# UPCNSL-ABS-PVC-DEP-1A.net
KiCad netlist of a schematic drawn in Altium Designer
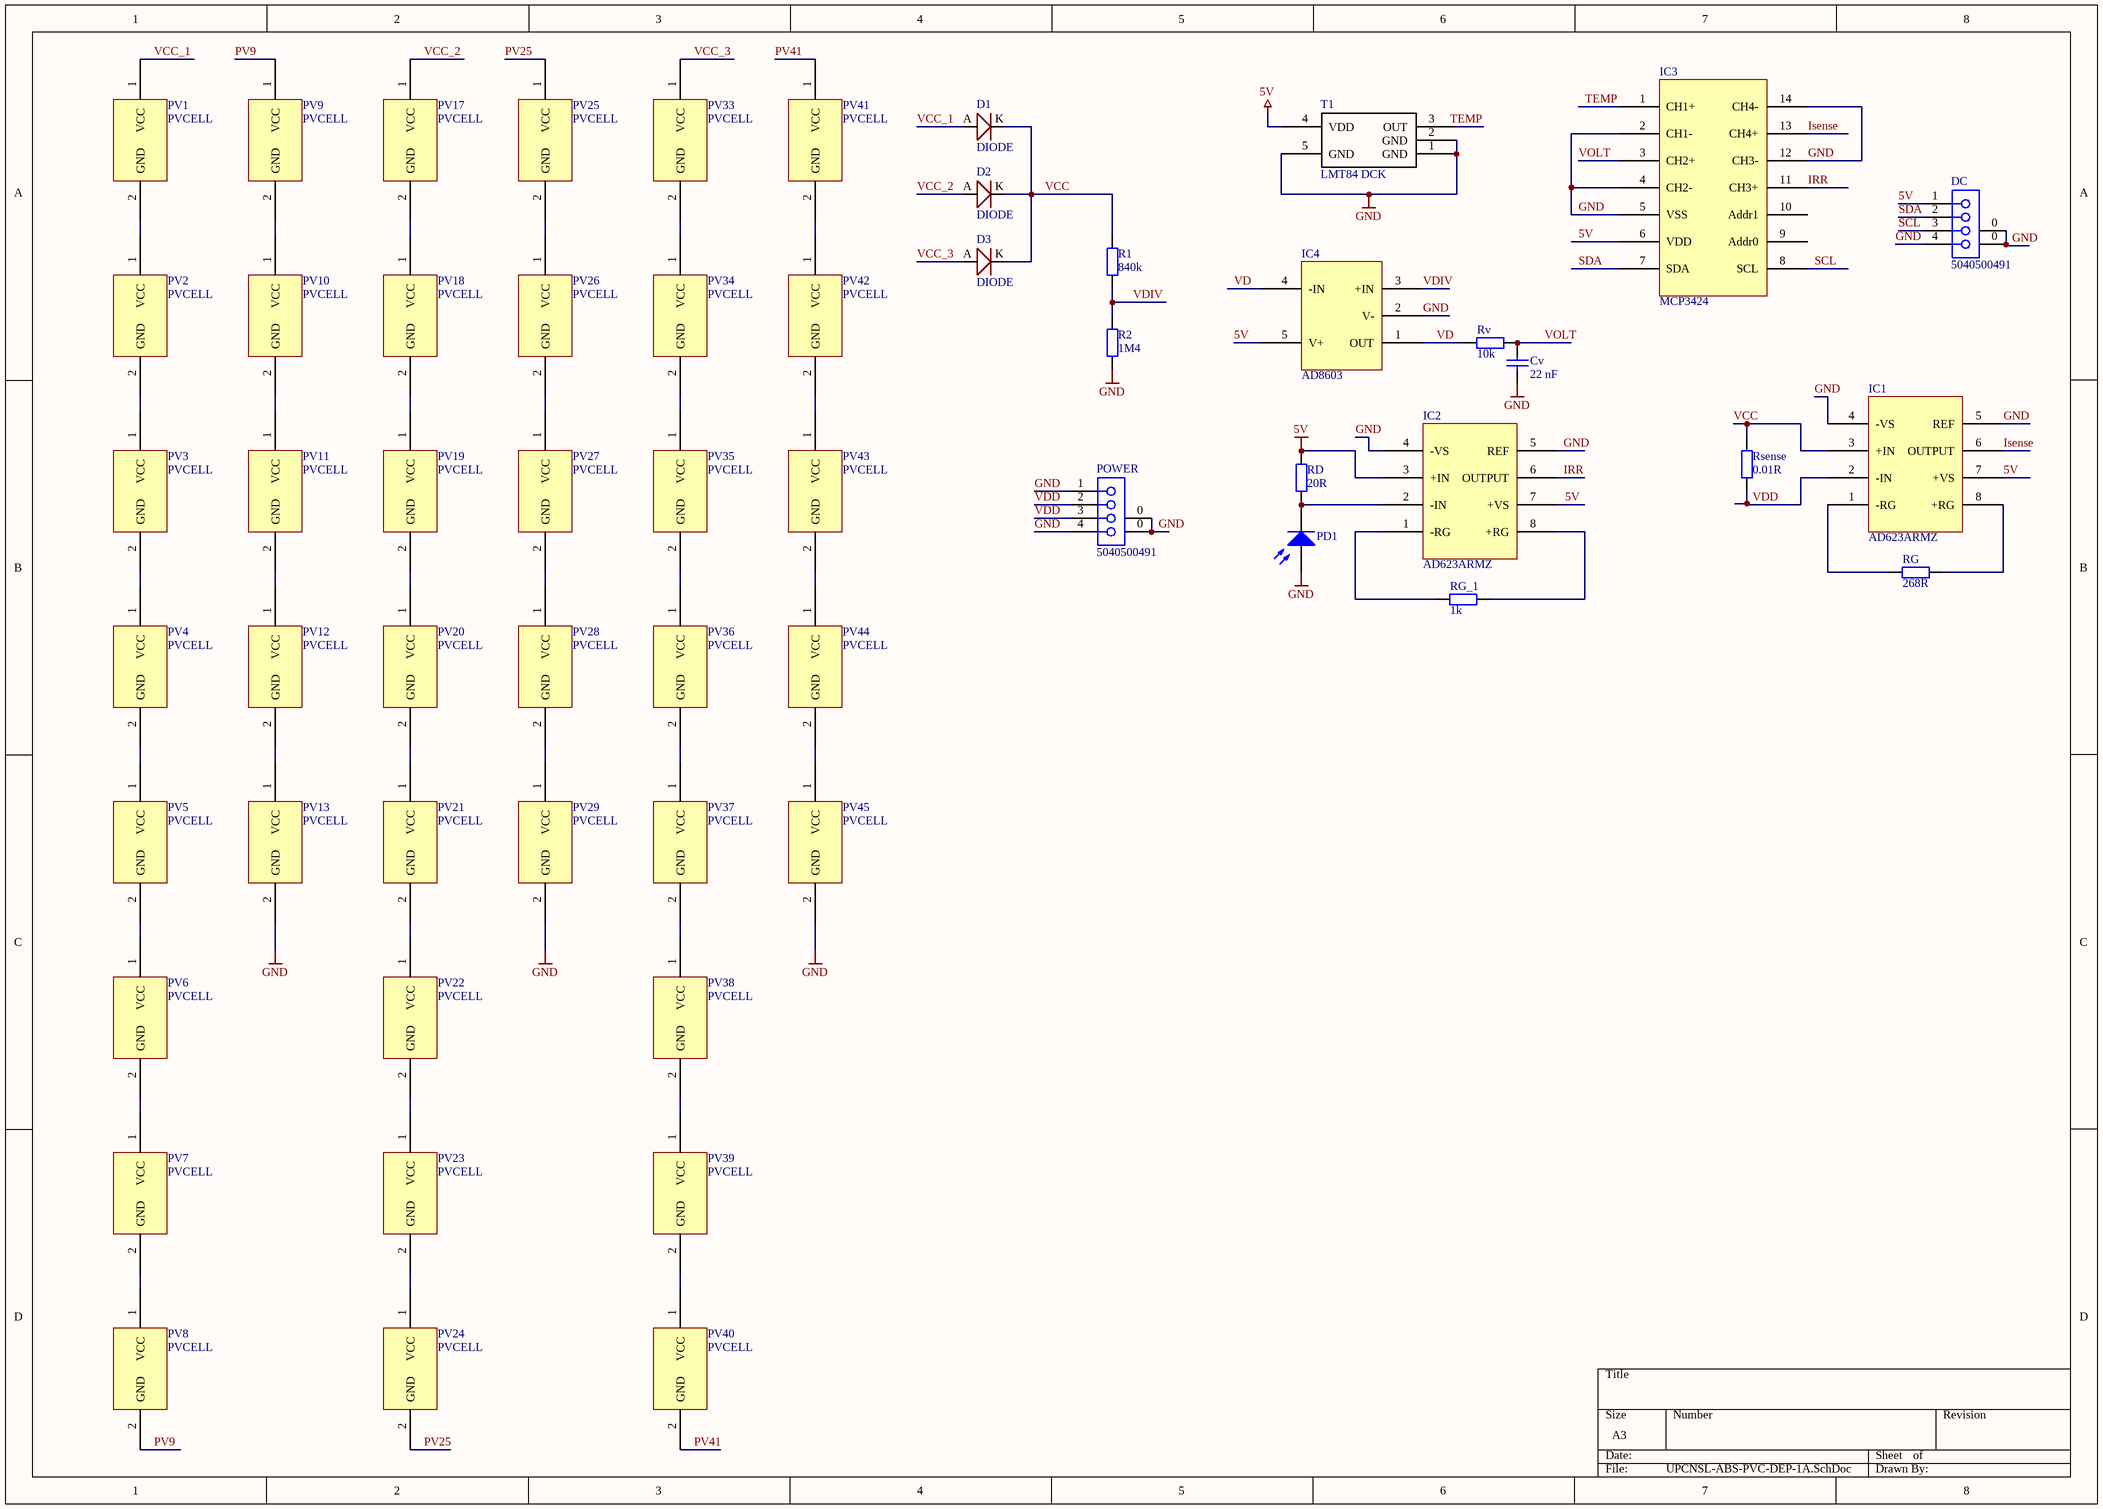
[diagram p0: UPCNSL-ABS-PVC-DEP-1A.SchDoc]

(export (version "E")
  (design (tool "Eeschema 10.0.6"))
  (components
    (comp (ref "Cv")
      (value "22 nF")
      (footprint "CAP0603")
      (description "Capacitor")
      (fields (field (name "Comment") "CAP0603"))
      (libsource (lib "UPCNSL-ABS-FLS-ARD_v1.2") (part "CAP0603"))
    )
    (comp (ref "D1")
      (value "DIODE")
      (footprint "(Schottky diode) SODFL160X70-2N")
      (libsource (lib "UPCNSL-ABS-FLS-ARD_v1.2") (part "DIODE"))
    )
    (comp (ref "D2")
      (value "DIODE")
      (footprint "(Schottky diode) SODFL160X70-2N")
      (libsource (lib "UPCNSL-ABS-FLS-ARD_v1.2") (part "DIODE"))
    )
    (comp (ref "D3")
      (value "DIODE")
      (footprint "(Schottky diode) SODFL160X70-2N")
      (libsource (lib "UPCNSL-ABS-FLS-ARD_v1.2") (part "DIODE"))
    )
    (comp (ref "DC")
      (value "5040500491")
      (footprint "5040500491")
      (libsource (lib "3CAT_Connectors") (part "MOLEX_5040500491"))
    )
    (comp (ref "IC1")
      (value "AD623ARMZ")
      (footprint "AD623ARMZ")
      (libsource (lib "UPCNSL-ABS-FLS-PVC") (part "AD623ARMZ"))
    )
    (comp (ref "IC2")
      (value "AD623ARMZ")
      (footprint "AD623ARMZ")
      (libsource (lib "UPCNSL-ABS-FLS-PVC") (part "AD623ARMZ"))
    )
    (comp (ref "IC3")
      (value "MCP3424")
      (footprint "MCP3424")
      (description "18-Bit, Multi-Channel ΔΣ Analog-to-Digital Converter with  I2C")
      (libsource (lib "UPCNSL-ABS-FLS-PVC") (part "MCP3424"))
    )
    (comp (ref "IC4")
      (value "AD8603")
      (footprint "AD8603")
      (libsource (lib "UPCNSL-ABS-FLS-PVC") (part "AD8603"))
    )
    (comp (ref "PD1")
      (value "Photo Sen")
      (footprint "C0805")
      (description "Photosensitive Diode")
      (fields (field (name "PUBLISHER") "Altium Limited"))
      (libsource (lib "Miscellaneous Devices") (part "Photo Sen"))
    )
    (comp (ref "POWER")
      (value "5040500491")
      (footprint "5040500491")
      (libsource (lib "3CAT_Connectors") (part "MOLEX_5040500491"))
    )
    (comp (ref "PV1")
      (value "PVCELL")
      (footprint "PV CELLS")
      (description "IXYS KXOB22-12X1L-ND")
      (libsource (lib "UPCNSL-ABS-FLS-PVC") (part "PVCELLS"))
    )
    (comp (ref "PV2")
      (value "PVCELL")
      (footprint "PV CELLS")
      (description "IXYS KXOB22-12X1L-ND")
      (libsource (lib "UPCNSL-ABS-FLS-PVC") (part "PVCELLS"))
    )
    (comp (ref "PV3")
      (value "PVCELL")
      (footprint "PV CELLS")
      (description "IXYS KXOB22-12X1L-ND")
      (libsource (lib "UPCNSL-ABS-FLS-PVC") (part "PVCELLS"))
    )
    (comp (ref "PV4")
      (value "PVCELL")
      (footprint "PV CELLS")
      (description "IXYS KXOB22-12X1L-ND")
      (libsource (lib "UPCNSL-ABS-FLS-PVC") (part "PVCELLS"))
    )
    (comp (ref "PV5")
      (value "PVCELL")
      (footprint "PV CELLS")
      (description "IXYS KXOB22-12X1L-ND")
      (libsource (lib "UPCNSL-ABS-FLS-PVC") (part "PVCELLS"))
    )
    (comp (ref "PV6")
      (value "PVCELL")
      (footprint "PV CELLS")
      (description "IXYS KXOB22-12X1L-ND")
      (libsource (lib "UPCNSL-ABS-FLS-PVC") (part "PVCELLS"))
    )
    (comp (ref "PV7")
      (value "PVCELL")
      (footprint "PV CELLS")
      (description "IXYS KXOB22-12X1L-ND")
      (libsource (lib "UPCNSL-ABS-FLS-PVC") (part "PVCELLS"))
    )
    (comp (ref "PV8")
      (value "PVCELL")
      (footprint "PV CELLS")
      (description "IXYS KXOB22-12X1L-ND")
      (libsource (lib "UPCNSL-ABS-FLS-PVC") (part "PVCELLS"))
    )
    (comp (ref "PV9")
      (value "PVCELL")
      (footprint "PV CELLS")
      (description "IXYS KXOB22-12X1L-ND")
      (libsource (lib "UPCNSL-ABS-FLS-PVC") (part "PVCELLS"))
    )
    (comp (ref "PV10")
      (value "PVCELL")
      (footprint "PV CELLS")
      (description "IXYS KXOB22-12X1L-ND")
      (libsource (lib "UPCNSL-ABS-FLS-PVC") (part "PVCELLS"))
    )
    (comp (ref "PV11")
      (value "PVCELL")
      (footprint "PV CELLS")
      (description "IXYS KXOB22-12X1L-ND")
      (libsource (lib "UPCNSL-ABS-FLS-PVC") (part "PVCELLS"))
    )
    (comp (ref "PV12")
      (value "PVCELL")
      (footprint "PV CELLS")
      (description "IXYS KXOB22-12X1L-ND")
      (libsource (lib "UPCNSL-ABS-FLS-PVC") (part "PVCELLS"))
    )
    (comp (ref "PV13")
      (value "PVCELL")
      (footprint "PV CELLS")
      (description "IXYS KXOB22-12X1L-ND")
      (libsource (lib "UPCNSL-ABS-FLS-PVC") (part "PVCELLS"))
    )
    (comp (ref "PV17")
      (value "PVCELL")
      (footprint "PV CELLS")
      (description "IXYS KXOB22-12X1L-ND")
      (libsource (lib "UPCNSL-ABS-FLS-PVC") (part "PVCELLS"))
    )
    (comp (ref "PV18")
      (value "PVCELL")
      (footprint "PV CELLS")
      (description "IXYS KXOB22-12X1L-ND")
      (libsource (lib "UPCNSL-ABS-FLS-PVC") (part "PVCELLS"))
    )
    (comp (ref "PV19")
      (value "PVCELL")
      (footprint "PV CELLS")
      (description "IXYS KXOB22-12X1L-ND")
      (libsource (lib "UPCNSL-ABS-FLS-PVC") (part "PVCELLS"))
    )
    (comp (ref "PV20")
      (value "PVCELL")
      (footprint "PV CELLS")
      (description "IXYS KXOB22-12X1L-ND")
      (libsource (lib "UPCNSL-ABS-FLS-PVC") (part "PVCELLS"))
    )
    (comp (ref "PV21")
      (value "PVCELL")
      (footprint "PV CELLS")
      (description "IXYS KXOB22-12X1L-ND")
      (libsource (lib "UPCNSL-ABS-FLS-PVC") (part "PVCELLS"))
    )
    (comp (ref "PV22")
      (value "PVCELL")
      (footprint "PV CELLS")
      (description "IXYS KXOB22-12X1L-ND")
      (libsource (lib "UPCNSL-ABS-FLS-PVC") (part "PVCELLS"))
    )
    (comp (ref "PV23")
      (value "PVCELL")
      (footprint "PV CELLS")
      (description "IXYS KXOB22-12X1L-ND")
      (libsource (lib "UPCNSL-ABS-FLS-PVC") (part "PVCELLS"))
    )
    (comp (ref "PV24")
      (value "PVCELL")
      (footprint "PV CELLS")
      (description "IXYS KXOB22-12X1L-ND")
      (libsource (lib "UPCNSL-ABS-FLS-PVC") (part "PVCELLS"))
    )
    (comp (ref "PV25")
      (value "PVCELL")
      (footprint "PV CELLS")
      (description "IXYS KXOB22-12X1L-ND")
      (libsource (lib "UPCNSL-ABS-FLS-PVC") (part "PVCELLS"))
    )
    (comp (ref "PV26")
      (value "PVCELL")
      (footprint "PV CELLS")
      (description "IXYS KXOB22-12X1L-ND")
      (libsource (lib "UPCNSL-ABS-FLS-PVC") (part "PVCELLS"))
    )
    (comp (ref "PV27")
      (value "PVCELL")
      (footprint "PV CELLS")
      (description "IXYS KXOB22-12X1L-ND")
      (libsource (lib "UPCNSL-ABS-FLS-PVC") (part "PVCELLS"))
    )
    (comp (ref "PV28")
      (value "PVCELL")
      (footprint "PV CELLS")
      (description "IXYS KXOB22-12X1L-ND")
      (libsource (lib "UPCNSL-ABS-FLS-PVC") (part "PVCELLS"))
    )
    (comp (ref "PV29")
      (value "PVCELL")
      (footprint "PV CELLS")
      (description "IXYS KXOB22-12X1L-ND")
      (libsource (lib "UPCNSL-ABS-FLS-PVC") (part "PVCELLS"))
    )
    (comp (ref "PV33")
      (value "PVCELL")
      (footprint "PV CELLS")
      (description "IXYS KXOB22-12X1L-ND")
      (libsource (lib "UPCNSL-ABS-FLS-PVC") (part "PVCELLS"))
    )
    (comp (ref "PV34")
      (value "PVCELL")
      (footprint "PV CELLS")
      (description "IXYS KXOB22-12X1L-ND")
      (libsource (lib "UPCNSL-ABS-FLS-PVC") (part "PVCELLS"))
    )
    (comp (ref "PV35")
      (value "PVCELL")
      (footprint "PV CELLS")
      (description "IXYS KXOB22-12X1L-ND")
      (libsource (lib "UPCNSL-ABS-FLS-PVC") (part "PVCELLS"))
    )
    (comp (ref "PV36")
      (value "PVCELL")
      (footprint "PV CELLS")
      (description "IXYS KXOB22-12X1L-ND")
      (libsource (lib "UPCNSL-ABS-FLS-PVC") (part "PVCELLS"))
    )
    (comp (ref "PV37")
      (value "PVCELL")
      (footprint "PV CELLS")
      (description "IXYS KXOB22-12X1L-ND")
      (libsource (lib "UPCNSL-ABS-FLS-PVC") (part "PVCELLS"))
    )
    (comp (ref "PV38")
      (value "PVCELL")
      (footprint "PV CELLS")
      (description "IXYS KXOB22-12X1L-ND")
      (libsource (lib "UPCNSL-ABS-FLS-PVC") (part "PVCELLS"))
    )
    (comp (ref "PV39")
      (value "PVCELL")
      (footprint "PV CELLS")
      (description "IXYS KXOB22-12X1L-ND")
      (libsource (lib "UPCNSL-ABS-FLS-PVC") (part "PVCELLS"))
    )
    (comp (ref "PV40")
      (value "PVCELL")
      (footprint "PV CELLS")
      (description "IXYS KXOB22-12X1L-ND")
      (libsource (lib "UPCNSL-ABS-FLS-PVC") (part "PVCELLS"))
    )
    (comp (ref "PV41")
      (value "PVCELL")
      (footprint "PV CELLS")
      (description "IXYS KXOB22-12X1L-ND")
      (libsource (lib "UPCNSL-ABS-FLS-PVC") (part "PVCELLS"))
    )
    (comp (ref "PV42")
      (value "PVCELL")
      (footprint "PV CELLS")
      (description "IXYS KXOB22-12X1L-ND")
      (libsource (lib "UPCNSL-ABS-FLS-PVC") (part "PVCELLS"))
    )
    (comp (ref "PV43")
      (value "PVCELL")
      (footprint "PV CELLS")
      (description "IXYS KXOB22-12X1L-ND")
      (libsource (lib "UPCNSL-ABS-FLS-PVC") (part "PVCELLS"))
    )
    (comp (ref "PV44")
      (value "PVCELL")
      (footprint "PV CELLS")
      (description "IXYS KXOB22-12X1L-ND")
      (libsource (lib "UPCNSL-ABS-FLS-PVC") (part "PVCELLS"))
    )
    (comp (ref "PV45")
      (value "PVCELL")
      (footprint "PV CELLS")
      (description "IXYS KXOB22-12X1L-ND")
      (libsource (lib "UPCNSL-ABS-FLS-PVC") (part "PVCELLS"))
    )
    (comp (ref "R1")
      (value "840k")
      (footprint "RES0603")
      (description "Resistor")
      (fields (field (name "Comment") "RES0603"))
      (libsource (lib "UPCNSL-ABS-FLS-ARD_v1.2") (part "RES0603"))
    )
    (comp (ref "R2")
      (value "1M4")
      (footprint "RES0603")
      (description "Resistor")
      (fields (field (name "Comment") "RES0603"))
      (libsource (lib "UPCNSL-ABS-FLS-ARD_v1.2") (part "RES0603"))
    )
    (comp (ref "RD")
      (value "20R")
      (footprint "RES0603")
      (description "Resistor")
      (fields (field (name "Comment") "RES0603"))
      (libsource (lib "UPCNSL-ABS-FLS-ARD_v1.2") (part "RES0603"))
    )
    (comp (ref "RG")
      (value "268R")
      (footprint "RES0603")
      (description "Resistor")
      (fields (field (name "Comment") "RES0603"))
      (libsource (lib "") (part "RES0603_1"))
    )
    (comp (ref "RG_1")
      (value "1k")
      (footprint "RES0603")
      (description "Resistor")
      (fields (field (name "Comment") "RES0603"))
      (libsource (lib "") (part "RES0603_1"))
    )
    (comp (ref "Rsense")
      (value "0.01R")
      (footprint "RES0603")
      (description "Resistor")
      (fields (field (name "Comment") "RES0603"))
      (libsource (lib "UPCNSL-ABS-FLS-ARD_v1.2") (part "RES0603"))
    )
    (comp (ref "Rv")
      (value "10k")
      (footprint "RES0603")
      (description "Resistor")
      (fields (field (name "Comment") "RES0603"))
      (libsource (lib "") (part "RES0603_1"))
    )
    (comp (ref "T1")
      (value "LMT84 DCK")
      (footprint "DCK/SOT65P210X110-5N")
      (libsource (lib "UPCNSL-ABS-FLS-PVC") (part "LMT84 DCK"))
    )
  )
  (nets
    (net (code "1") (name "/IRR") (class "Default")
      (node (ref "IC2") (pin "6") (pinfunction "OUTPUT_6") (pintype "passive"))
      (node (ref "IC3") (pin "11") (pinfunction "CH3+_11") (pintype "passive"))
    )
    (net (code "2") (name "/Isense") (class "Default")
      (node (ref "IC1") (pin "6") (pinfunction "OUTPUT_6") (pintype "passive"))
      (node (ref "IC3") (pin "13") (pinfunction "CH4+_13") (pintype "passive"))
    )
    (net (code "3") (name "/PV9") (class "Default")
      (node (ref "PV8") (pin "2") (pinfunction "GND_2") (pintype "passive"))
      (node (ref "PV9") (pin "1") (pinfunction "VCC_1") (pintype "passive"))
    )
    (net (code "4") (name "/PV25") (class "Default")
      (node (ref "PV24") (pin "2") (pinfunction "GND_2") (pintype "passive"))
      (node (ref "PV25") (pin "1") (pinfunction "VCC_1") (pintype "passive"))
    )
    (net (code "5") (name "/PV41") (class "Default")
      (node (ref "PV40") (pin "2") (pinfunction "GND_2") (pintype "passive"))
      (node (ref "PV41") (pin "1") (pinfunction "VCC_1") (pintype "passive"))
    )
    (net (code "6") (name "/SCL") (class "Default")
      (node (ref "DC") (pin "3") (pinfunction "3_3") (pintype "passive"))
      (node (ref "IC3") (pin "8") (pinfunction "SCL_8") (pintype "passive"))
    )
    (net (code "7") (name "/SDA") (class "Default")
      (node (ref "DC") (pin "2") (pinfunction "2_2") (pintype "passive"))
      (node (ref "IC3") (pin "7") (pinfunction "SDA_7") (pintype "passive"))
    )
    (net (code "8") (name "/TEMP") (class "Default")
      (node (ref "IC3") (pin "1") (pinfunction "CH1+_1") (pintype "passive"))
    )
    (net (code "9") (name "/VCC") (class "Default")
      (node (ref "D1") (pin "K") (pinfunction "K_K") (pintype "passive"))
      (node (ref "D2") (pin "K") (pinfunction "K_K") (pintype "passive"))
      (node (ref "D3") (pin "K") (pinfunction "K_K") (pintype "passive"))
      (node (ref "IC1") (pin "3") (pinfunction "+IN_3") (pintype "passive"))
      (node (ref "R1") (pin "2") (pinfunction "2_2") (pintype "passive"))
      (node (ref "Rsense") (pin "2") (pinfunction "2_2") (pintype "passive"))
    )
    (net (code "10") (name "/VCC_1") (class "Default")
      (node (ref "D1") (pin "A") (pinfunction "A_A") (pintype "passive"))
      (node (ref "PV1") (pin "1") (pinfunction "VCC_1") (pintype "passive"))
    )
    (net (code "11") (name "/VCC_2") (class "Default")
      (node (ref "D2") (pin "A") (pinfunction "A_A") (pintype "passive"))
      (node (ref "PV17") (pin "1") (pinfunction "VCC_1") (pintype "passive"))
    )
    (net (code "12") (name "/VCC_3") (class "Default")
      (node (ref "D3") (pin "A") (pinfunction "A_A") (pintype "passive"))
      (node (ref "PV33") (pin "1") (pinfunction "VCC_1") (pintype "passive"))
    )
    (net (code "13") (name "/VD") (class "Default")
      (node (ref "IC4") (pin "1") (pinfunction "OUT_1") (pintype "passive"))
      (node (ref "IC4") (pin "4") (pinfunction "-IN_4") (pintype "passive"))
      (node (ref "Rv") (pin "1") (pinfunction "1_1") (pintype "passive"))
    )
    (net (code "14") (name "/VDD") (class "Default")
      (node (ref "IC1") (pin "2") (pinfunction "-IN_2") (pintype "passive"))
      (node (ref "POWER") (pin "2") (pinfunction "2_2") (pintype "passive"))
      (node (ref "POWER") (pin "3") (pinfunction "3_3") (pintype "passive"))
      (node (ref "Rsense") (pin "1") (pinfunction "1_1") (pintype "passive"))
    )
    (net (code "15") (name "/VDIV") (class "Default")
      (node (ref "IC4") (pin "3") (pinfunction "+IN_3") (pintype "passive"))
      (node (ref "R1") (pin "1") (pinfunction "1_1") (pintype "passive"))
      (node (ref "R2") (pin "2") (pinfunction "2_2") (pintype "passive"))
    )
    (net (code "16") (name "/VOLT") (class "Default")
      (node (ref "Cv") (pin "2") (pinfunction "2_2") (pintype "passive"))
      (node (ref "IC3") (pin "3") (pinfunction "CH2+_3") (pintype "passive"))
      (node (ref "Rv") (pin "2") (pinfunction "2_2") (pintype "passive"))
    )
    (net (code "17") (name "5V") (class "Default")
      (node (ref "DC") (pin "1") (pinfunction "1_1") (pintype "passive"))
      (node (ref "IC1") (pin "7") (pinfunction "+VS_7") (pintype "passive"))
      (node (ref "IC2") (pin "3") (pinfunction "+IN_3") (pintype "passive"))
      (node (ref "IC2") (pin "7") (pinfunction "+VS_7") (pintype "passive"))
      (node (ref "IC3") (pin "6") (pinfunction "VDD_6") (pintype "passive"))
      (node (ref "IC4") (pin "5") (pinfunction "V+_5") (pintype "passive"))
      (node (ref "RD") (pin "2") (pinfunction "2_2") (pintype "passive"))
      (node (ref "T1") (pin "4") (pinfunction "VDD_4") (pintype "passive"))
    )
    (net (code "18") (name "GND") (class "Default")
      (node (ref "Cv") (pin "1") (pinfunction "1_1") (pintype "passive"))
      (node (ref "DC") (pin "0") (pinfunction "MH1_0") (pintype "passive"))
      (node (ref "DC") (pin "4") (pinfunction "4_4") (pintype "passive"))
      (node (ref "IC1") (pin "4") (pinfunction "-VS_4") (pintype "passive"))
      (node (ref "IC1") (pin "5") (pinfunction "REF_5") (pintype "passive"))
      (node (ref "IC2") (pin "4") (pinfunction "-VS_4") (pintype "passive"))
      (node (ref "IC2") (pin "5") (pinfunction "REF_5") (pintype "passive"))
      (node (ref "IC3") (pin "12") (pinfunction "CH3-_12") (pintype "passive"))
      (node (ref "IC3") (pin "14") (pinfunction "CH4-_14") (pintype "passive"))
      (node (ref "IC3") (pin "2") (pinfunction "CH1-_2") (pintype "passive"))
      (node (ref "IC3") (pin "4") (pinfunction "CH2-_4") (pintype "passive"))
      (node (ref "IC3") (pin "5") (pinfunction "VSS_5") (pintype "passive"))
      (node (ref "IC4") (pin "2") (pinfunction "V-_2") (pintype "passive"))
      (node (ref "PD1") (pin "1") (pinfunction "A_1") (pintype "passive"))
      (node (ref "POWER") (pin "0") (pinfunction "MH2_0") (pintype "passive"))
      (node (ref "POWER") (pin "1") (pinfunction "1_1") (pintype "passive"))
      (node (ref "POWER") (pin "4") (pinfunction "4_4") (pintype "passive"))
      (node (ref "PV13") (pin "2") (pinfunction "GND_2") (pintype "passive"))
      (node (ref "PV29") (pin "2") (pinfunction "GND_2") (pintype "passive"))
      (node (ref "PV45") (pin "2") (pinfunction "GND_2") (pintype "passive"))
      (node (ref "R2") (pin "1") (pinfunction "1_1") (pintype "passive"))
      (node (ref "T1") (pin "1") (pinfunction "GND_1") (pintype "passive"))
      (node (ref "T1") (pin "2") (pinfunction "GND_2") (pintype "passive"))
      (node (ref "T1") (pin "5") (pinfunction "GND_5") (pintype "passive"))
    )
    (net (code "19") (name "Net-(IC1-+RG)") (class "Default")
      (node (ref "IC1") (pin "8") (pinfunction "+RG_8") (pintype "passive"))
      (node (ref "RG") (pin "2") (pinfunction "2_2") (pintype "passive"))
    )
    (net (code "20") (name "Net-(IC1--RG)") (class "Default")
      (node (ref "IC1") (pin "1") (pinfunction "-RG_1") (pintype "passive"))
      (node (ref "RG") (pin "1") (pinfunction "1_1") (pintype "passive"))
    )
    (net (code "21") (name "Net-(IC2-+RG)") (class "Default")
      (node (ref "IC2") (pin "8") (pinfunction "+RG_8") (pintype "passive"))
      (node (ref "RG_1") (pin "2") (pinfunction "2_2") (pintype "passive"))
    )
    (net (code "22") (name "Net-(IC2--IN)") (class "Default")
      (node (ref "IC2") (pin "2") (pinfunction "-IN_2") (pintype "passive"))
      (node (ref "PD1") (pin "2") (pinfunction "K_2") (pintype "passive"))
      (node (ref "RD") (pin "1") (pinfunction "1_1") (pintype "passive"))
    )
    (net (code "23") (name "Net-(IC2--RG)") (class "Default")
      (node (ref "IC2") (pin "1") (pinfunction "-RG_1") (pintype "passive"))
      (node (ref "RG_1") (pin "1") (pinfunction "1_1") (pintype "passive"))
    )
    (net (code "24") (name "Net-(PV1-GND)") (class "Default")
      (node (ref "PV1") (pin "2") (pinfunction "GND_2") (pintype "passive"))
      (node (ref "PV2") (pin "1") (pinfunction "VCC_1") (pintype "passive"))
    )
    (net (code "25") (name "Net-(PV2-GND)") (class "Default")
      (node (ref "PV2") (pin "2") (pinfunction "GND_2") (pintype "passive"))
      (node (ref "PV3") (pin "1") (pinfunction "VCC_1") (pintype "passive"))
    )
    (net (code "26") (name "Net-(PV3-GND)") (class "Default")
      (node (ref "PV3") (pin "2") (pinfunction "GND_2") (pintype "passive"))
      (node (ref "PV4") (pin "1") (pinfunction "VCC_1") (pintype "passive"))
    )
    (net (code "27") (name "Net-(PV4-GND)") (class "Default")
      (node (ref "PV4") (pin "2") (pinfunction "GND_2") (pintype "passive"))
      (node (ref "PV5") (pin "1") (pinfunction "VCC_1") (pintype "passive"))
    )
    (net (code "28") (name "Net-(PV5-GND)") (class "Default")
      (node (ref "PV5") (pin "2") (pinfunction "GND_2") (pintype "passive"))
      (node (ref "PV6") (pin "1") (pinfunction "VCC_1") (pintype "passive"))
    )
    (net (code "29") (name "Net-(PV6-GND)") (class "Default")
      (node (ref "PV6") (pin "2") (pinfunction "GND_2") (pintype "passive"))
      (node (ref "PV7") (pin "1") (pinfunction "VCC_1") (pintype "passive"))
    )
    (net (code "30") (name "Net-(PV7-GND)") (class "Default")
      (node (ref "PV7") (pin "2") (pinfunction "GND_2") (pintype "passive"))
      (node (ref "PV8") (pin "1") (pinfunction "VCC_1") (pintype "passive"))
    )
    (net (code "31") (name "Net-(PV10-GND)") (class "Default")
      (node (ref "PV10") (pin "2") (pinfunction "GND_2") (pintype "passive"))
      (node (ref "PV11") (pin "1") (pinfunction "VCC_1") (pintype "passive"))
    )
    (net (code "32") (name "Net-(PV10-VCC)") (class "Default")
      (node (ref "PV10") (pin "1") (pinfunction "VCC_1") (pintype "passive"))
      (node (ref "PV9") (pin "2") (pinfunction "GND_2") (pintype "passive"))
    )
    (net (code "33") (name "Net-(PV11-GND)") (class "Default")
      (node (ref "PV11") (pin "2") (pinfunction "GND_2") (pintype "passive"))
      (node (ref "PV12") (pin "1") (pinfunction "VCC_1") (pintype "passive"))
    )
    (net (code "34") (name "Net-(PV12-GND)") (class "Default")
      (node (ref "PV12") (pin "2") (pinfunction "GND_2") (pintype "passive"))
      (node (ref "PV13") (pin "1") (pinfunction "VCC_1") (pintype "passive"))
    )
    (net (code "35") (name "Net-(PV17-GND)") (class "Default")
      (node (ref "PV17") (pin "2") (pinfunction "GND_2") (pintype "passive"))
      (node (ref "PV18") (pin "1") (pinfunction "VCC_1") (pintype "passive"))
    )
    (net (code "36") (name "Net-(PV18-GND)") (class "Default")
      (node (ref "PV18") (pin "2") (pinfunction "GND_2") (pintype "passive"))
      (node (ref "PV19") (pin "1") (pinfunction "VCC_1") (pintype "passive"))
    )
    (net (code "37") (name "Net-(PV19-GND)") (class "Default")
      (node (ref "PV19") (pin "2") (pinfunction "GND_2") (pintype "passive"))
      (node (ref "PV20") (pin "1") (pinfunction "VCC_1") (pintype "passive"))
    )
    (net (code "38") (name "Net-(PV20-GND)") (class "Default")
      (node (ref "PV20") (pin "2") (pinfunction "GND_2") (pintype "passive"))
      (node (ref "PV21") (pin "1") (pinfunction "VCC_1") (pintype "passive"))
    )
    (net (code "39") (name "Net-(PV21-GND)") (class "Default")
      (node (ref "PV21") (pin "2") (pinfunction "GND_2") (pintype "passive"))
      (node (ref "PV22") (pin "1") (pinfunction "VCC_1") (pintype "passive"))
    )
    (net (code "40") (name "Net-(PV22-GND)") (class "Default")
      (node (ref "PV22") (pin "2") (pinfunction "GND_2") (pintype "passive"))
      (node (ref "PV23") (pin "1") (pinfunction "VCC_1") (pintype "passive"))
    )
    (net (code "41") (name "Net-(PV23-GND)") (class "Default")
      (node (ref "PV23") (pin "2") (pinfunction "GND_2") (pintype "passive"))
      (node (ref "PV24") (pin "1") (pinfunction "VCC_1") (pintype "passive"))
    )
    (net (code "42") (name "Net-(PV25-GND)") (class "Default")
      (node (ref "PV25") (pin "2") (pinfunction "GND_2") (pintype "passive"))
      (node (ref "PV26") (pin "1") (pinfunction "VCC_1") (pintype "passive"))
    )
    (net (code "43") (name "Net-(PV26-GND)") (class "Default")
      (node (ref "PV26") (pin "2") (pinfunction "GND_2") (pintype "passive"))
      (node (ref "PV27") (pin "1") (pinfunction "VCC_1") (pintype "passive"))
    )
    (net (code "44") (name "Net-(PV27-GND)") (class "Default")
      (node (ref "PV27") (pin "2") (pinfunction "GND_2") (pintype "passive"))
      (node (ref "PV28") (pin "1") (pinfunction "VCC_1") (pintype "passive"))
    )
    (net (code "45") (name "Net-(PV28-GND)") (class "Default")
      (node (ref "PV28") (pin "2") (pinfunction "GND_2") (pintype "passive"))
      (node (ref "PV29") (pin "1") (pinfunction "VCC_1") (pintype "passive"))
    )
    (net (code "46") (name "Net-(PV33-GND)") (class "Default")
      (node (ref "PV33") (pin "2") (pinfunction "GND_2") (pintype "passive"))
      (node (ref "PV34") (pin "1") (pinfunction "VCC_1") (pintype "passive"))
    )
    (net (code "47") (name "Net-(PV34-GND)") (class "Default")
      (node (ref "PV34") (pin "2") (pinfunction "GND_2") (pintype "passive"))
      (node (ref "PV35") (pin "1") (pinfunction "VCC_1") (pintype "passive"))
    )
    (net (code "48") (name "Net-(PV35-GND)") (class "Default")
      (node (ref "PV35") (pin "2") (pinfunction "GND_2") (pintype "passive"))
      (node (ref "PV36") (pin "1") (pinfunction "VCC_1") (pintype "passive"))
    )
    (net (code "49") (name "Net-(PV36-GND)") (class "Default")
      (node (ref "PV36") (pin "2") (pinfunction "GND_2") (pintype "passive"))
      (node (ref "PV37") (pin "1") (pinfunction "VCC_1") (pintype "passive"))
    )
    (net (code "50") (name "Net-(PV37-GND)") (class "Default")
      (node (ref "PV37") (pin "2") (pinfunction "GND_2") (pintype "passive"))
      (node (ref "PV38") (pin "1") (pinfunction "VCC_1") (pintype "passive"))
    )
    (net (code "51") (name "Net-(PV38-GND)") (class "Default")
      (node (ref "PV38") (pin "2") (pinfunction "GND_2") (pintype "passive"))
      (node (ref "PV39") (pin "1") (pinfunction "VCC_1") (pintype "passive"))
    )
    (net (code "52") (name "Net-(PV39-GND)") (class "Default")
      (node (ref "PV39") (pin "2") (pinfunction "GND_2") (pintype "passive"))
      (node (ref "PV40") (pin "1") (pinfunction "VCC_1") (pintype "passive"))
    )
    (net (code "53") (name "Net-(PV41-GND)") (class "Default")
      (node (ref "PV41") (pin "2") (pinfunction "GND_2") (pintype "passive"))
      (node (ref "PV42") (pin "1") (pinfunction "VCC_1") (pintype "passive"))
    )
    (net (code "54") (name "Net-(PV42-GND)") (class "Default")
      (node (ref "PV42") (pin "2") (pinfunction "GND_2") (pintype "passive"))
      (node (ref "PV43") (pin "1") (pinfunction "VCC_1") (pintype "passive"))
    )
    (net (code "55") (name "Net-(PV43-GND)") (class "Default")
      (node (ref "PV43") (pin "2") (pinfunction "GND_2") (pintype "passive"))
      (node (ref "PV44") (pin "1") (pinfunction "VCC_1") (pintype "passive"))
    )
    (net (code "56") (name "Net-(PV44-GND)") (class "Default")
      (node (ref "PV44") (pin "2") (pinfunction "GND_2") (pintype "passive"))
      (node (ref "PV45") (pin "1") (pinfunction "VCC_1") (pintype "passive"))
    )
    (net (code "57") (name "unconnected-(IC3-Addr0-Pad9)") (class "Default")
      (node (ref "IC3") (pin "9") (pinfunction "Addr0_9") (pintype "passive"))
    )
    (net (code "58") (name "unconnected-(IC3-Addr1-Pad10)") (class "Default")
      (node (ref "IC3") (pin "10") (pinfunction "Addr1_10") (pintype "passive"))
    )
    (net (code "59") (name "unconnected-(T1-OUT-Pad3)") (class "Default")
      (node (ref "T1") (pin "3") (pinfunction "OUT_3") (pintype "passive"))
    )
  )
)
